# BNO055imuModule.net
KiCad netlist of a schematic drawn in Altium Designer
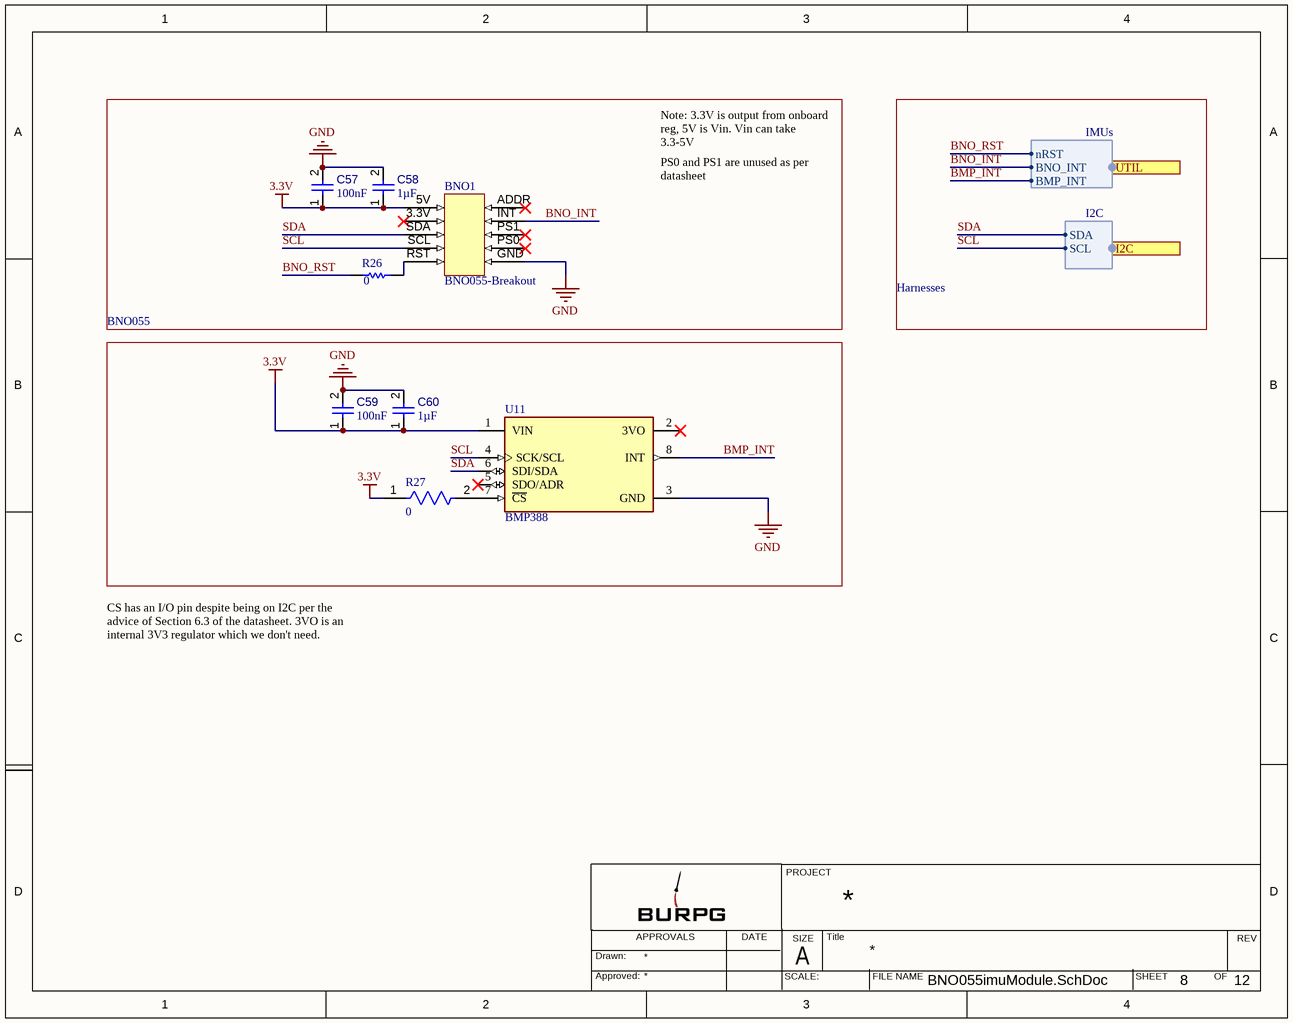
[diagram p0: BNO055imuModule.SchDoc]

(export (version "E")
  (design (tool "Eeschema 10.0.6"))
  (components
    (comp (ref "BNO1")
      (value "BNO055-Breakout")
      (footprint "2472-Footprint-1")
      (description "Adafruit 9-Dof Absolute Orientation Imu Fusion Breakout - Bno055 Rohs Compliant: Yes")
      (libsource (lib "Boston University") (part "2472-Symbol-1"))
    )
    (comp (ref "C57")
      (value "100nF")
      (footprint "CAPC2013X95X50LL10T25")
      (description "Chip Capacitor, 100 nF, +/- 10%, 50 V, 0805 (2012 Metric)")
      (fields (field (name "TOLERANCE") "10%") (field (name "Comment") "Capacitor 100 nF +/-10% 50 V 0805"))
      (libsource (lib "Boston University") (part "CAP-NP-2"))
    )
    (comp (ref "C58")
      (value "1µF")
      (footprint "CAPC2013X135X45NL10T25")
      (description "Chip Capacitor, 1 uF, +/- 10%, 50 V, 0805 (2012 Metric)")
      (fields (field (name "TOLERANCE") "10%") (field (name "Comment") "Capacitor 1 uF +/- 10% 50 V 0805"))
      (libsource (lib "Boston University") (part "CAP-NP-2"))
    )
    (comp (ref "C59")
      (value "100nF")
      (footprint "CAPC2013X95X50LL10T25")
      (description "Chip Capacitor, 100 nF, +/- 10%, 50 V, 0805 (2012 Metric)")
      (fields (field (name "TOLERANCE") "10%") (field (name "Comment") "Capacitor 100 nF +/-10% 50 V 0805"))
      (libsource (lib "Boston University") (part "CAP-NP-2"))
    )
    (comp (ref "C60")
      (value "1µF")
      (footprint "CAPC2013X135X45NL10T25")
      (description "Chip Capacitor, 1 uF, +/- 10%, 50 V, 0805 (2012 Metric)")
      (fields (field (name "TOLERANCE") "10%") (field (name "Comment") "Capacitor 1 uF +/- 10% 50 V 0805"))
      (libsource (lib "Boston University") (part "CAP-NP-2"))
    )
    (comp (ref "R26")
      (value "0")
      (footprint "RESC3116X70X50ML13T20")
      (description "Chip Resistor, 0 Ohm, 0.25 W, -55 to 155 degC, 1206 (3216 Metric)")
      (fields (field (name "TOLERANCE") "0.05%") (field (name "POWER") "250mW"))
      (libsource (lib "Boston University") (part "RES-2"))
    )
    (comp (ref "R27")
      (value "0")
      (footprint "FP-CRCW1206-e3-MFG")
      (description "RES Thick Film, 0Ω, 0.25W, 1206")
      (libsource (lib "Altium Content Vault") (part "1029c3af85768c4190bb7ad29bc67b5"))
    )
    (comp (ref "U11")
      (value "BMP388")
      (footprint "FP-3966-MFG")
      (description "BMP388 - PRECISION BAROMETRIC PR")
      (libsource (lib "Altium Content Vault") (part "7ec954515874f1695838194320a9f7f"))
    )
  )
  (nets
    (net (code "3") (name "/BMP_INT") (class "Default")
      (node (ref "U11") (pin "8") (pinfunction "INT_8") (pintype "output"))
    )
    (net (code "4") (name "/BNO_INT") (class "Default") (node (ref "BNO1") (pin "INT") (pintype "input")))
    (net (code "5") (name "/BNO_RST") (class "Default")
      (node (ref "R26") (pin "1") (pinfunction "1_1") (pintype "passive"))
    )
    (net (code "6") (name "/SCL") (class "Default")
      (node (ref "BNO1") (pin "SCL") (pintype "input"))
      (node (ref "U11") (pin "4") (pinfunction "SCK/SCL_4") (pintype "input"))
    )
    (net (code "7") (name "/SDA") (class "Default")
      (node (ref "BNO1") (pin "SDA") (pintype "input"))
      (node (ref "U11") (pin "6") (pinfunction "SDI/SDA_6") (pintype "bidirectional"))
    )
    (net (code "10") (name "3.3V") (class "Default")
      (node (ref "BNO1") (pin "5V") (pintype "input"))
      (node (ref "C57") (pin "1") (pinfunction "1_1") (pintype "passive"))
      (node (ref "C58") (pin "1") (pinfunction "1_1") (pintype "passive"))
      (node (ref "C59") (pin "1") (pinfunction "1_1") (pintype "passive"))
      (node (ref "C60") (pin "1") (pinfunction "1_1") (pintype "passive"))
      (node (ref "R27") (pin "1") (pinfunction "1_1") (pintype "passive"))
      (node (ref "U11") (pin "1") (pinfunction "VIN_1") (pintype "power_in"))
    )
    (net (code "11") (name "GND") (class "Default")
      (node (ref "BNO1") (pin "GND") (pintype "input"))
      (node (ref "C57") (pin "2") (pinfunction "2_2") (pintype "passive"))
      (node (ref "C58") (pin "2") (pinfunction "2_2") (pintype "passive"))
      (node (ref "C59") (pin "2") (pinfunction "2_2") (pintype "passive"))
      (node (ref "C60") (pin "2") (pinfunction "2_2") (pintype "passive"))
      (node (ref "U11") (pin "3") (pinfunction "GND_3") (pintype "power_in"))
    )
    (net (code "12") (name "Net-(BNO1-PadRST)") (class "Default")
      (node (ref "BNO1") (pin "RST") (pintype "input"))
      (node (ref "R26") (pin "2") (pinfunction "2_2") (pintype "passive"))
    )
    (net (code "13") (name "Net-(U11-~{CS})") (class "Default")
      (node (ref "R27") (pin "2") (pinfunction "2_2") (pintype "passive"))
      (node (ref "U11") (pin "7") (pinfunction "~{CS}_7") (pintype "input"))
    )
    (net (code "14") (name "unconnected-(BNO1-Pad3.3V)") (class "Default")
      (node (ref "BNO1") (pin "3.3V") (pintype "input+no_connect"))
    )
    (net (code "15") (name "unconnected-(BNO1-PadADDR)") (class "Default")
      (node (ref "BNO1") (pin "ADDR") (pintype "input+no_connect"))
    )
    (net (code "16") (name "unconnected-(BNO1-PadPS0)") (class "Default")
      (node (ref "BNO1") (pin "PS0") (pintype "input+no_connect"))
    )
    (net (code "17") (name "unconnected-(BNO1-PadPS1)") (class "Default")
      (node (ref "BNO1") (pin "PS1") (pintype "input+no_connect"))
    )
    (net (code "18") (name "unconnected-(U11-3VO-Pad2)") (class "Default")
      (node (ref "U11") (pin "2") (pinfunction "3VO_2") (pintype "power_in+no_connect"))
    )
    (net (code "19") (name "unconnected-(U11-SDO{slash}ADR-Pad5)") (class "Default")
      (node (ref "U11") (pin "5") (pinfunction "SDO/ADR_5") (pintype "bidirectional+no_connect"))
    )
  )
)
